# D2000_micro.net
KiCad netlist of a schematic drawn in Altium Designer
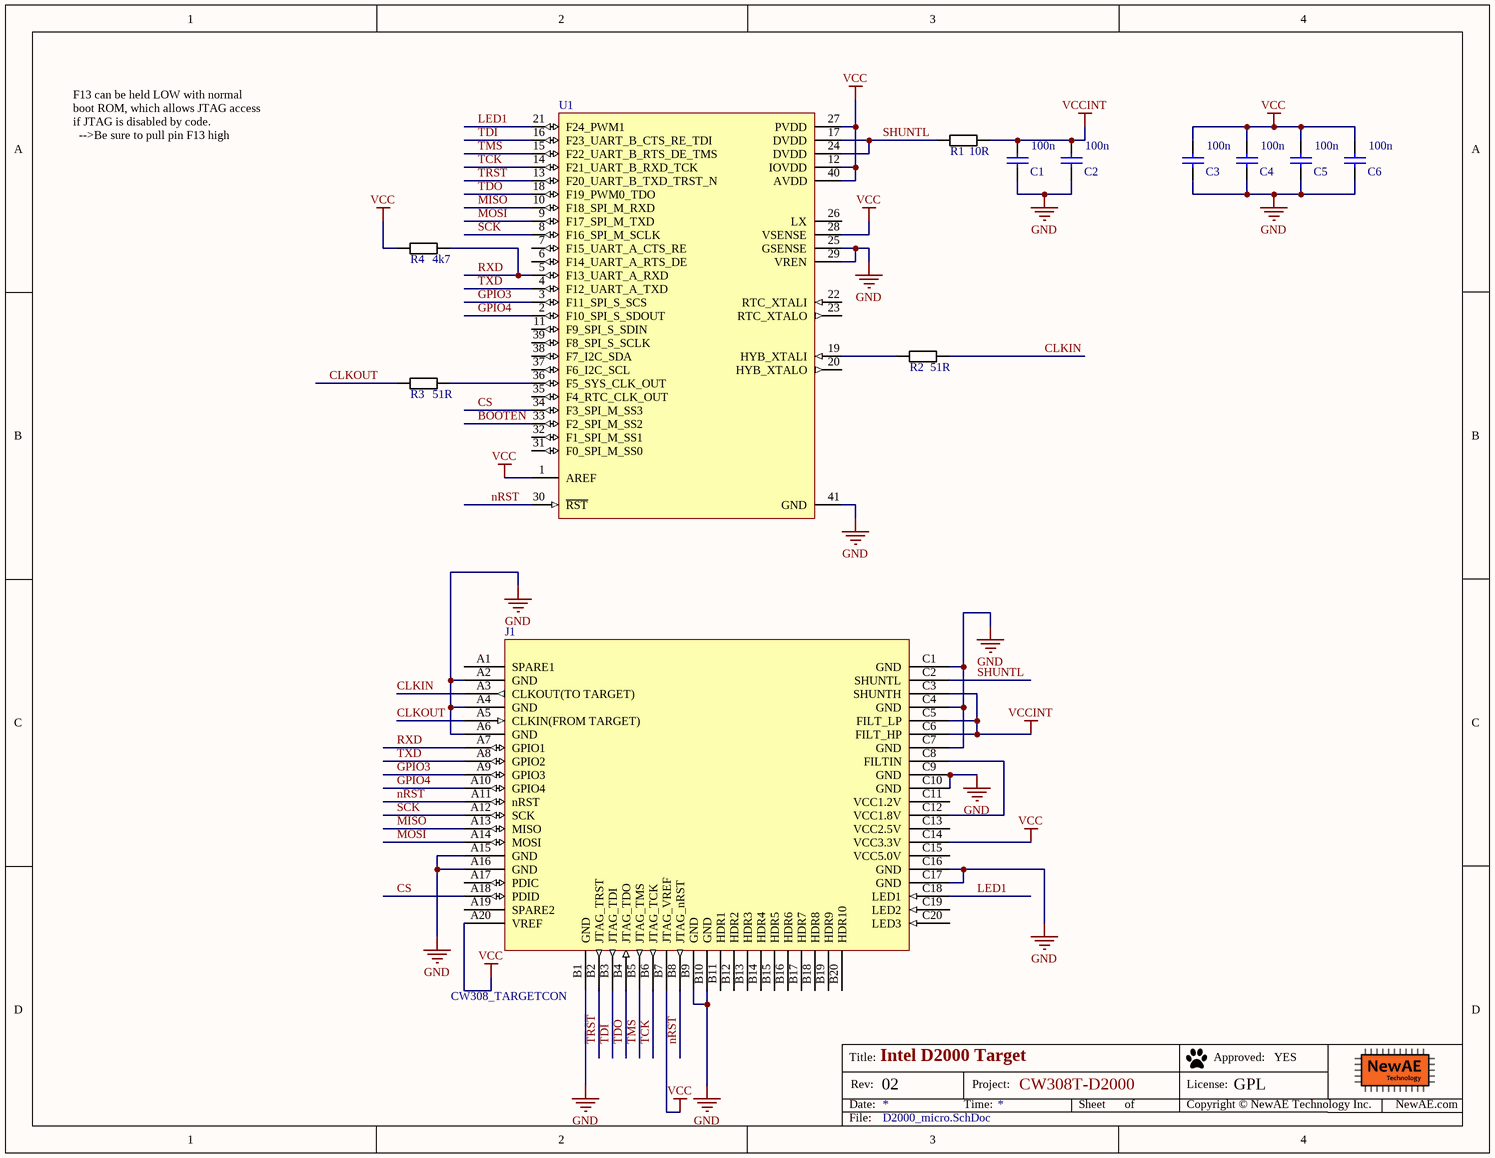
[diagram p0: D2000_micro.SchDoc]

(export (version "E")
  (design (tool "Eeschema 10.0.6"))
  (components
    (comp (ref "C1")
      (value "100n")
      (footprint "CAPC0603_M")
      (description "100n, 0603")
      (fields (field (name "PART NUMBER") "CCHIP-100n-0603"))
      (libsource (lib "altium-import") (part "root_1_CAP_"))
    )
    (comp (ref "C2")
      (value "100n")
      (footprint "CAPC0603_M")
      (description "100n, 0603")
      (fields (field (name "PART NUMBER") "CCHIP-100n-0603"))
      (libsource (lib "altium-import") (part "root_1_CAP_"))
    )
    (comp (ref "C3")
      (value "100n")
      (footprint "CAPC0603_M")
      (description "100n, 0603")
      (fields (field (name "PART NUMBER") "CCHIP-100n-0603"))
      (libsource (lib "altium-import") (part "root_1_CAP_"))
    )
    (comp (ref "C4")
      (value "100n")
      (footprint "CAPC0603_M")
      (description "100n, 0603")
      (fields (field (name "PART NUMBER") "CCHIP-100n-0603"))
      (libsource (lib "altium-import") (part "root_1_CAP_"))
    )
    (comp (ref "C5")
      (value "100n")
      (footprint "CAPC0603_M")
      (description "100n, 0603")
      (fields (field (name "PART NUMBER") "CCHIP-100n-0603"))
      (libsource (lib "altium-import") (part "root_1_CAP_"))
    )
    (comp (ref "C6")
      (value "100n")
      (footprint "CAPC0603_M")
      (description "100n, 0603")
      (fields (field (name "PART NUMBER") "CCHIP-100n-0603"))
      (libsource (lib "altium-import") (part "root_1_CAP_"))
    )
    (comp (ref "J1")
      (value "CW308_TARGETCON")
      (footprint "ChipWhisperer_AltiumLib:CW308_TBOARD_CONN")
      (description "CW308 \"Standard\" Target Board Connector")
      (libsource (lib "ChipWhisperer_AltiumLib") (part "CW308_TBOARD"))
    )
    (comp (ref "R1")
      (value "10R")
      (footprint "RESC1608X55N")
      (description "10R, 0603")
      (fields (field (name "PART NUMBER") "RCHIP-10R-0603"))
      (libsource (lib "NewAE_AltiumLib") (part "RES-EU"))
    )
    (comp (ref "R2")
      (value "51R")
      (footprint "RESC1608X55N")
      (description "51R, 0603")
      (fields (field (name "PART NUMBER") "RCHIP-51R-0603"))
      (libsource (lib "NewAE_AltiumLib") (part "RES-EU"))
    )
    (comp (ref "R3")
      (value "51R")
      (footprint "RESC1608X55N")
      (description "51R, 0603")
      (fields (field (name "PART NUMBER") "RCHIP-51R-0603"))
      (libsource (lib "NewAE_AltiumLib") (part "RES-EU"))
    )
    (comp (ref "R4")
      (value "4k7")
      (footprint "RESC1608X55N")
      (description "4k7 res, 0603, 1%, 1/10W")
      (fields (field (name "PART NUMBER") "RCHIP-4K7-0603") (field (name "TOLERANCE") "1%"))
      (libsource (lib "NewAE_AltiumLib") (part "RES-EU"))
    )
    (comp (ref "U1")
      (value "FND2000")
      (footprint "QFN50P595X595X90_HS-41M")
      (description "Intel x86 microcontroller")
      (fields (field (name "PART NUMBER") "D2000"))
      (libsource (lib "NewAE_AltiumLib") (part "D2000"))
    )
  )
  (nets
    (net (code "1") (name "/BOOTEN") (class "Default")
      (node (ref "U1") (pin "33") (pinfunction "F2_SPI_M_SS2_33") (pintype "bidirectional"))
    )
    (net (code "2") (name "/CLKIN") (class "Default")
      (node (ref "J1") (pin "A3") (pinfunction "CLKOUT(TO_TARGET)_A3") (pintype "output"))
      (node (ref "R2") (pin "2") (pinfunction "2_2") (pintype "passive"))
    )
    (net (code "3") (name "/CLKOUT") (class "Default")
      (node (ref "J1") (pin "A5") (pinfunction "CLKIN(FROM_TARGET)_A5") (pintype "input"))
      (node (ref "R3") (pin "1") (pinfunction "1_1") (pintype "passive"))
    )
    (net (code "4") (name "/CS") (class "Default")
      (node (ref "J1") (pin "A18") (pinfunction "PDID_A18") (pintype "bidirectional"))
      (node (ref "U1") (pin "34") (pinfunction "F3_SPI_M_SS3_34") (pintype "bidirectional"))
    )
    (net (code "5") (name "/GPIO3") (class "Default")
      (node (ref "J1") (pin "A9") (pinfunction "GPIO3_A9") (pintype "bidirectional"))
      (node (ref "U1") (pin "3") (pinfunction "F11_SPI_S_SCS_3") (pintype "bidirectional"))
    )
    (net (code "6") (name "/GPIO4") (class "Default")
      (node (ref "J1") (pin "A10") (pinfunction "GPIO4_A10") (pintype "bidirectional"))
      (node (ref "U1") (pin "2") (pinfunction "F10_SPI_S_SDOUT_2") (pintype "bidirectional"))
    )
    (net (code "7") (name "/LED1") (class "Default")
      (node (ref "J1") (pin "C18") (pinfunction "LED1_C18") (pintype "input"))
      (node (ref "U1") (pin "21") (pinfunction "F24_PWM1_21") (pintype "bidirectional"))
    )
    (net (code "8") (name "/MISO") (class "Default")
      (node (ref "J1") (pin "A13") (pinfunction "MISO_A13") (pintype "bidirectional"))
      (node (ref "U1") (pin "10") (pinfunction "F18_SPI_M_RXD_10") (pintype "bidirectional"))
    )
    (net (code "9") (name "/MOSI") (class "Default")
      (node (ref "J1") (pin "A14") (pinfunction "MOSI_A14") (pintype "bidirectional"))
      (node (ref "U1") (pin "9") (pinfunction "F17_SPI_M_TXD_9") (pintype "bidirectional"))
    )
    (net (code "10") (name "/RXD") (class "Default")
      (node (ref "J1") (pin "A7") (pinfunction "GPIO1_A7") (pintype "bidirectional"))
      (node (ref "R4") (pin "2") (pinfunction "2_2") (pintype "passive"))
      (node (ref "U1") (pin "5") (pinfunction "F13_UART_A_RXD_5") (pintype "bidirectional"))
    )
    (net (code "11") (name "/SCK") (class "Default")
      (node (ref "J1") (pin "A12") (pinfunction "SCK_A12") (pintype "bidirectional"))
      (node (ref "U1") (pin "8") (pinfunction "F16_SPI_M_SCLK_8") (pintype "bidirectional"))
    )
    (net (code "12") (name "/SHUNTL") (class "Default")
      (node (ref "J1") (pin "C2") (pinfunction "SHUNTL_C2") (pintype "passive"))
      (node (ref "R1") (pin "1") (pinfunction "1_1") (pintype "passive"))
      (node (ref "U1") (pin "17") (pinfunction "DVDD_17") (pintype "power_in"))
      (node (ref "U1") (pin "24") (pinfunction "DVDD_24") (pintype "power_in"))
    )
    (net (code "13") (name "/TCK") (class "Default")
      (node (ref "J1") (pin "B6") (pinfunction "JTAG_TCK_B6") (pintype "output"))
      (node (ref "U1") (pin "14") (pinfunction "F21_UART_B_RXD_TCK_14") (pintype "bidirectional"))
    )
    (net (code "14") (name "/TDI") (class "Default")
      (node (ref "J1") (pin "B3") (pinfunction "JTAG_TDI_B3") (pintype "output"))
      (node (ref "U1") (pin "16") (pinfunction "F23_UART_B_CTS_RE_TDI_16") (pintype "bidirectional"))
    )
    (net (code "15") (name "/TDO") (class "Default")
      (node (ref "J1") (pin "B4") (pinfunction "JTAG_TDO_B4") (pintype "input"))
      (node (ref "U1") (pin "18") (pinfunction "F19_PWM0_TDO_18") (pintype "bidirectional"))
    )
    (net (code "16") (name "/TMS") (class "Default")
      (node (ref "J1") (pin "B5") (pinfunction "JTAG_TMS_B5") (pintype "output"))
      (node (ref "U1") (pin "15") (pinfunction "F22_UART_B_RTS_DE_TMS_15") (pintype "bidirectional"))
    )
    (net (code "17") (name "/TRST") (class "Default")
      (node (ref "J1") (pin "B2") (pinfunction "JTAG_TRST_B2") (pintype "output"))
      (node (ref "U1") (pin "13") (pinfunction "F20_UART_B_TXD_TRST_N_13") (pintype "bidirectional"))
    )
    (net (code "18") (name "/TXD") (class "Default")
      (node (ref "J1") (pin "A8") (pinfunction "GPIO2_A8") (pintype "bidirectional"))
      (node (ref "U1") (pin "4") (pinfunction "F12_UART_A_TXD_4") (pintype "bidirectional"))
    )
    (net (code "19") (name "/nRST") (class "Default")
      (node (ref "J1") (pin "A11") (pinfunction "nRST_A11") (pintype "bidirectional"))
      (node (ref "J1") (pin "B8") (pinfunction "JTAG_nRST_B8") (pintype "output"))
      (node (ref "U1") (pin "30") (pinfunction "~{RST}_30") (pintype "input"))
    )
    (net (code "20") (name "GND") (class "Default")
      (node (ref "C1") (pin "2") (pinfunction "2_2") (pintype "passive"))
      (node (ref "C2") (pin "2") (pinfunction "2_2") (pintype "passive"))
      (node (ref "C3") (pin "2") (pinfunction "2_2") (pintype "passive"))
      (node (ref "C4") (pin "2") (pinfunction "2_2") (pintype "passive"))
      (node (ref "C5") (pin "2") (pinfunction "2_2") (pintype "passive"))
      (node (ref "C6") (pin "2") (pinfunction "2_2") (pintype "passive"))
      (node (ref "J1") (pin "A15") (pinfunction "GND_A15") (pintype "passive"))
      (node (ref "J1") (pin "A16") (pinfunction "GND_A16") (pintype "passive"))
      (node (ref "J1") (pin "A2") (pinfunction "GND_A2") (pintype "passive"))
      (node (ref "J1") (pin "A4") (pinfunction "GND_A4") (pintype "passive"))
      (node (ref "J1") (pin "A6") (pinfunction "GND_A6") (pintype "power_in"))
      (node (ref "J1") (pin "B1") (pinfunction "GND_B1") (pintype "passive"))
      (node (ref "J1") (pin "B10") (pinfunction "GND_B10") (pintype "passive"))
      (node (ref "J1") (pin "B9") (pinfunction "GND_B9") (pintype "passive"))
      (node (ref "J1") (pin "C1") (pinfunction "GND_C1") (pintype "power_in"))
      (node (ref "J1") (pin "C10") (pinfunction "GND_C10") (pintype "power_in"))
      (node (ref "J1") (pin "C16") (pinfunction "GND_C16") (pintype "power_in"))
      (node (ref "J1") (pin "C17") (pinfunction "GND_C17") (pintype "power_in"))
      (node (ref "J1") (pin "C4") (pinfunction "GND_C4") (pintype "power_in"))
      (node (ref "J1") (pin "C7") (pinfunction "GND_C7") (pintype "power_in"))
      (node (ref "J1") (pin "C9") (pinfunction "GND_C9") (pintype "power_in"))
      (node (ref "U1") (pin "25") (pinfunction "GSENSE_25") (pintype "passive"))
      (node (ref "U1") (pin "29") (pinfunction "VREN_29") (pintype "passive"))
      (node (ref "U1") (pin "41") (pinfunction "GND_41") (pintype "power_in"))
    )
    (net (code "21") (name "Net-(J1-FILTIN)") (class "Default")
      (node (ref "J1") (pin "C12") (pinfunction "VCC1.8V_C12") (pintype "power_in"))
      (node (ref "J1") (pin "C8") (pinfunction "FILTIN_C8") (pintype "passive"))
    )
    (net (code "22") (name "Net-(U1-F5_SYS_CLK_OUT)") (class "Default")
      (node (ref "R3") (pin "2") (pinfunction "2_2") (pintype "passive"))
      (node (ref "U1") (pin "36") (pinfunction "F5_SYS_CLK_OUT_36") (pintype "bidirectional"))
    )
    (net (code "23") (name "Net-(U1-HYB_XTALI)") (class "Default")
      (node (ref "R2") (pin "1") (pinfunction "1_1") (pintype "passive"))
      (node (ref "U1") (pin "19") (pinfunction "HYB_XTALI_19") (pintype "input"))
    )
    (net (code "24") (name "VCC") (class "Default")
      (node (ref "C3") (pin "1") (pinfunction "1_1") (pintype "passive"))
      (node (ref "C4") (pin "1") (pinfunction "1_1") (pintype "passive"))
      (node (ref "C5") (pin "1") (pinfunction "1_1") (pintype "passive"))
      (node (ref "C6") (pin "1") (pinfunction "1_1") (pintype "passive"))
      (node (ref "J1") (pin "A20") (pinfunction "VREF_A20") (pintype "tri_state"))
      (node (ref "J1") (pin "B7") (pinfunction "JTAG_VREF_B7") (pintype "tri_state"))
      (node (ref "J1") (pin "C14") (pinfunction "VCC3.3V_C14") (pintype "power_in"))
      (node (ref "R4") (pin "1") (pinfunction "1_1") (pintype "passive"))
      (node (ref "U1") (pin "1") (pinfunction "AREF_1") (pintype "passive"))
      (node (ref "U1") (pin "12") (pinfunction "IOVDD_12") (pintype "power_in"))
      (node (ref "U1") (pin "27") (pinfunction "PVDD_27") (pintype "power_in"))
      (node (ref "U1") (pin "28") (pinfunction "VSENSE_28") (pintype "passive"))
      (node (ref "U1") (pin "40") (pinfunction "AVDD_40") (pintype "power_in"))
    )
    (net (code "25") (name "VCCINT") (class "Default")
      (node (ref "C1") (pin "1") (pinfunction "1_1") (pintype "passive"))
      (node (ref "C2") (pin "1") (pinfunction "1_1") (pintype "passive"))
      (node (ref "J1") (pin "C3") (pinfunction "SHUNTH_C3") (pintype "passive"))
      (node (ref "J1") (pin "C5") (pinfunction "FILT_LP_C5") (pintype "passive"))
      (node (ref "J1") (pin "C6") (pinfunction "FILT_HP_C6") (pintype "passive"))
      (node (ref "R1") (pin "2") (pinfunction "2_2") (pintype "passive"))
    )
    (net (code "26") (name "unconnected-(J1-HDR1-PadB11)") (class "Default")
      (node (ref "J1") (pin "B11") (pinfunction "HDR1_B11") (pintype "passive"))
    )
    (net (code "27") (name "unconnected-(J1-HDR2-PadB12)") (class "Default")
      (node (ref "J1") (pin "B12") (pinfunction "HDR2_B12") (pintype "passive"))
    )
    (net (code "28") (name "unconnected-(J1-HDR3-PadB13)") (class "Default")
      (node (ref "J1") (pin "B13") (pinfunction "HDR3_B13") (pintype "passive"))
    )
    (net (code "29") (name "unconnected-(J1-HDR4-PadB14)") (class "Default")
      (node (ref "J1") (pin "B14") (pinfunction "HDR4_B14") (pintype "passive"))
    )
    (net (code "30") (name "unconnected-(J1-HDR5-PadB15)") (class "Default")
      (node (ref "J1") (pin "B15") (pinfunction "HDR5_B15") (pintype "passive"))
    )
    (net (code "31") (name "unconnected-(J1-HDR6-PadB16)") (class "Default")
      (node (ref "J1") (pin "B16") (pinfunction "HDR6_B16") (pintype "passive"))
    )
    (net (code "32") (name "unconnected-(J1-HDR7-PadB17)") (class "Default")
      (node (ref "J1") (pin "B17") (pinfunction "HDR7_B17") (pintype "passive"))
    )
    (net (code "33") (name "unconnected-(J1-HDR8-PadB18)") (class "Default")
      (node (ref "J1") (pin "B18") (pinfunction "HDR8_B18") (pintype "passive"))
    )
    (net (code "34") (name "unconnected-(J1-HDR9-PadB19)") (class "Default")
      (node (ref "J1") (pin "B19") (pinfunction "HDR9_B19") (pintype "passive"))
    )
    (net (code "35") (name "unconnected-(J1-HDR10-PadB20)") (class "Default")
      (node (ref "J1") (pin "B20") (pinfunction "HDR10_B20") (pintype "passive"))
    )
    (net (code "36") (name "unconnected-(J1-LED2-PadC19)") (class "Default")
      (node (ref "J1") (pin "C19") (pinfunction "LED2_C19") (pintype "input"))
    )
    (net (code "37") (name "unconnected-(J1-LED3-PadC20)") (class "Default")
      (node (ref "J1") (pin "C20") (pinfunction "LED3_C20") (pintype "input"))
    )
    (net (code "38") (name "unconnected-(J1-PDIC-PadA17)") (class "Default")
      (node (ref "J1") (pin "A17") (pinfunction "PDIC_A17") (pintype "bidirectional"))
    )
    (net (code "39") (name "unconnected-(J1-SPARE1-PadA1)") (class "Default")
      (node (ref "J1") (pin "A1") (pinfunction "SPARE1_A1") (pintype "passive"))
    )
    (net (code "40") (name "unconnected-(J1-SPARE2-PadA19)") (class "Default")
      (node (ref "J1") (pin "A19") (pinfunction "SPARE2_A19") (pintype "passive"))
    )
    (net (code "41") (name "unconnected-(J1-VCC1.2V-PadC11)") (class "Default")
      (node (ref "J1") (pin "C11") (pinfunction "VCC1.2V_C11") (pintype "power_in"))
    )
    (net (code "42") (name "unconnected-(J1-VCC2.5V-PadC13)") (class "Default")
      (node (ref "J1") (pin "C13") (pinfunction "VCC2.5V_C13") (pintype "power_in"))
    )
    (net (code "43") (name "unconnected-(J1-VCC5.0V-PadC15)") (class "Default")
      (node (ref "J1") (pin "C15") (pinfunction "VCC5.0V_C15") (pintype "power_in"))
    )
    (net (code "44") (name "unconnected-(U1-F0_SPI_M_SS0-Pad31)") (class "Default")
      (node (ref "U1") (pin "31") (pinfunction "F0_SPI_M_SS0_31") (pintype "bidirectional"))
    )
    (net (code "45") (name "unconnected-(U1-F1_SPI_M_SS1-Pad32)") (class "Default")
      (node (ref "U1") (pin "32") (pinfunction "F1_SPI_M_SS1_32") (pintype "bidirectional"))
    )
    (net (code "46") (name "unconnected-(U1-F4_RTC_CLK_OUT-Pad35)") (class "Default")
      (node (ref "U1") (pin "35") (pinfunction "F4_RTC_CLK_OUT_35") (pintype "bidirectional"))
    )
    (net (code "47") (name "unconnected-(U1-F6_I2C_SCL-Pad37)") (class "Default")
      (node (ref "U1") (pin "37") (pinfunction "F6_I2C_SCL_37") (pintype "bidirectional"))
    )
    (net (code "48") (name "unconnected-(U1-F7_I2C_SDA-Pad38)") (class "Default")
      (node (ref "U1") (pin "38") (pinfunction "F7_I2C_SDA_38") (pintype "bidirectional"))
    )
    (net (code "49") (name "unconnected-(U1-F8_SPI_S_SCLK-Pad39)") (class "Default")
      (node (ref "U1") (pin "39") (pinfunction "F8_SPI_S_SCLK_39") (pintype "bidirectional"))
    )
    (net (code "50") (name "unconnected-(U1-F9_SPI_S_SDIN-Pad11)") (class "Default")
      (node (ref "U1") (pin "11") (pinfunction "F9_SPI_S_SDIN_11") (pintype "bidirectional"))
    )
    (net (code "51") (name "unconnected-(U1-F14_UART_A_RTS_DE-Pad6)") (class "Default")
      (node (ref "U1") (pin "6") (pinfunction "F14_UART_A_RTS_DE_6") (pintype "bidirectional"))
    )
    (net (code "52") (name "unconnected-(U1-F15_UART_A_CTS_RE-Pad7)") (class "Default")
      (node (ref "U1") (pin "7") (pinfunction "F15_UART_A_CTS_RE_7") (pintype "bidirectional"))
    )
    (net (code "53") (name "unconnected-(U1-HYB_XTALO-Pad20)") (class "Default")
      (node (ref "U1") (pin "20") (pinfunction "HYB_XTALO_20") (pintype "output"))
    )
    (net (code "54") (name "unconnected-(U1-LX-Pad26)") (class "Default")
      (node (ref "U1") (pin "26") (pinfunction "LX_26") (pintype "passive"))
    )
    (net (code "55") (name "unconnected-(U1-RTC_XTALI-Pad22)") (class "Default")
      (node (ref "U1") (pin "22") (pinfunction "RTC_XTALI_22") (pintype "input"))
    )
    (net (code "56") (name "unconnected-(U1-RTC_XTALO-Pad23)") (class "Default")
      (node (ref "U1") (pin "23") (pinfunction "RTC_XTALO_23") (pintype "output"))
    )
  )
)
